# NXPESC-UF1_test003.net
KiCad netlist of a schematic drawn in EAGLE
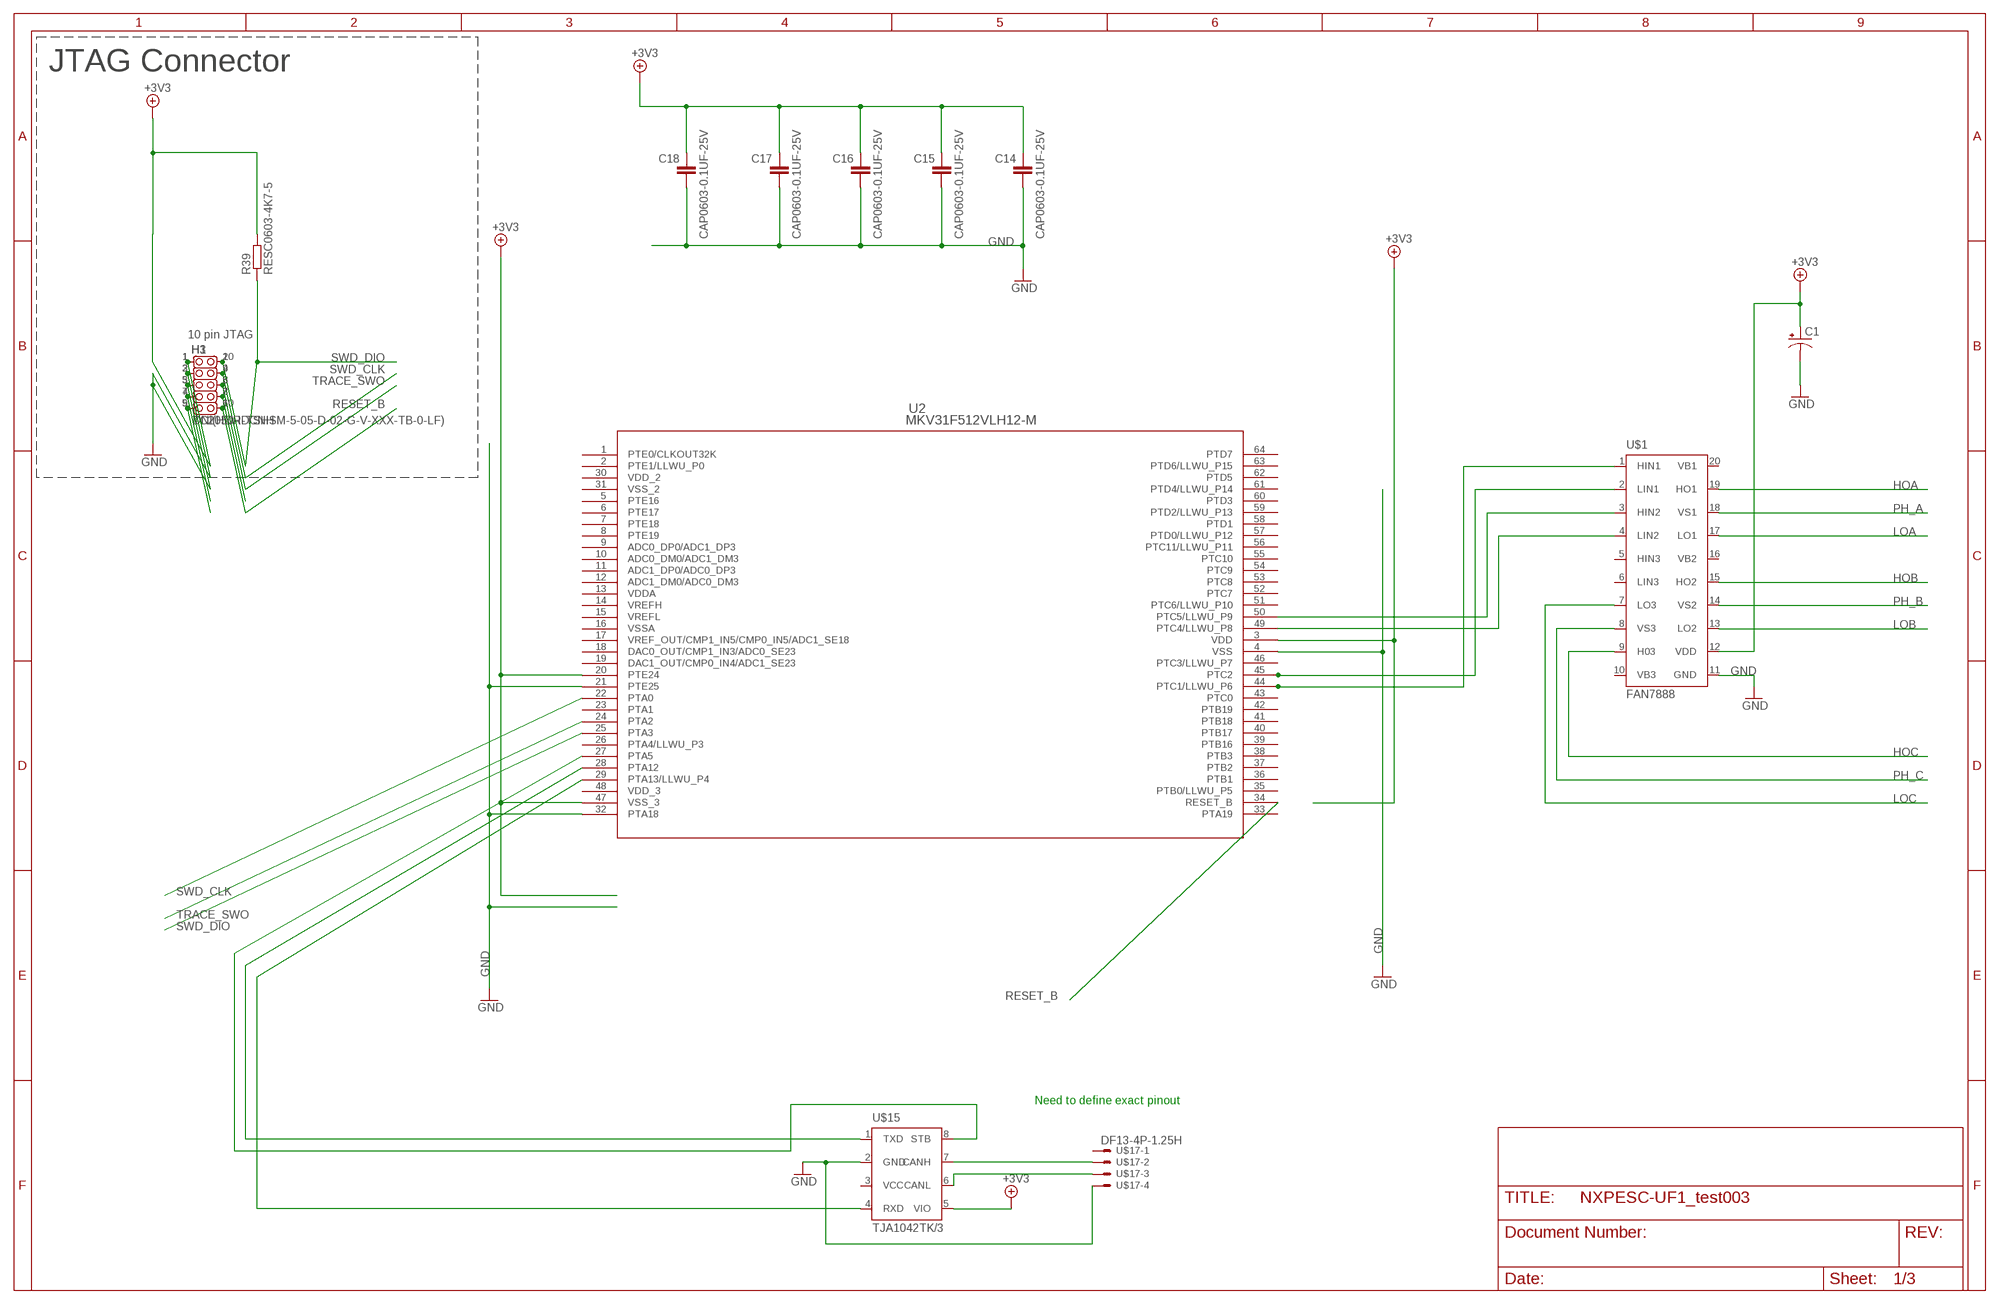
[diagram p0: schematic, sheet 1]
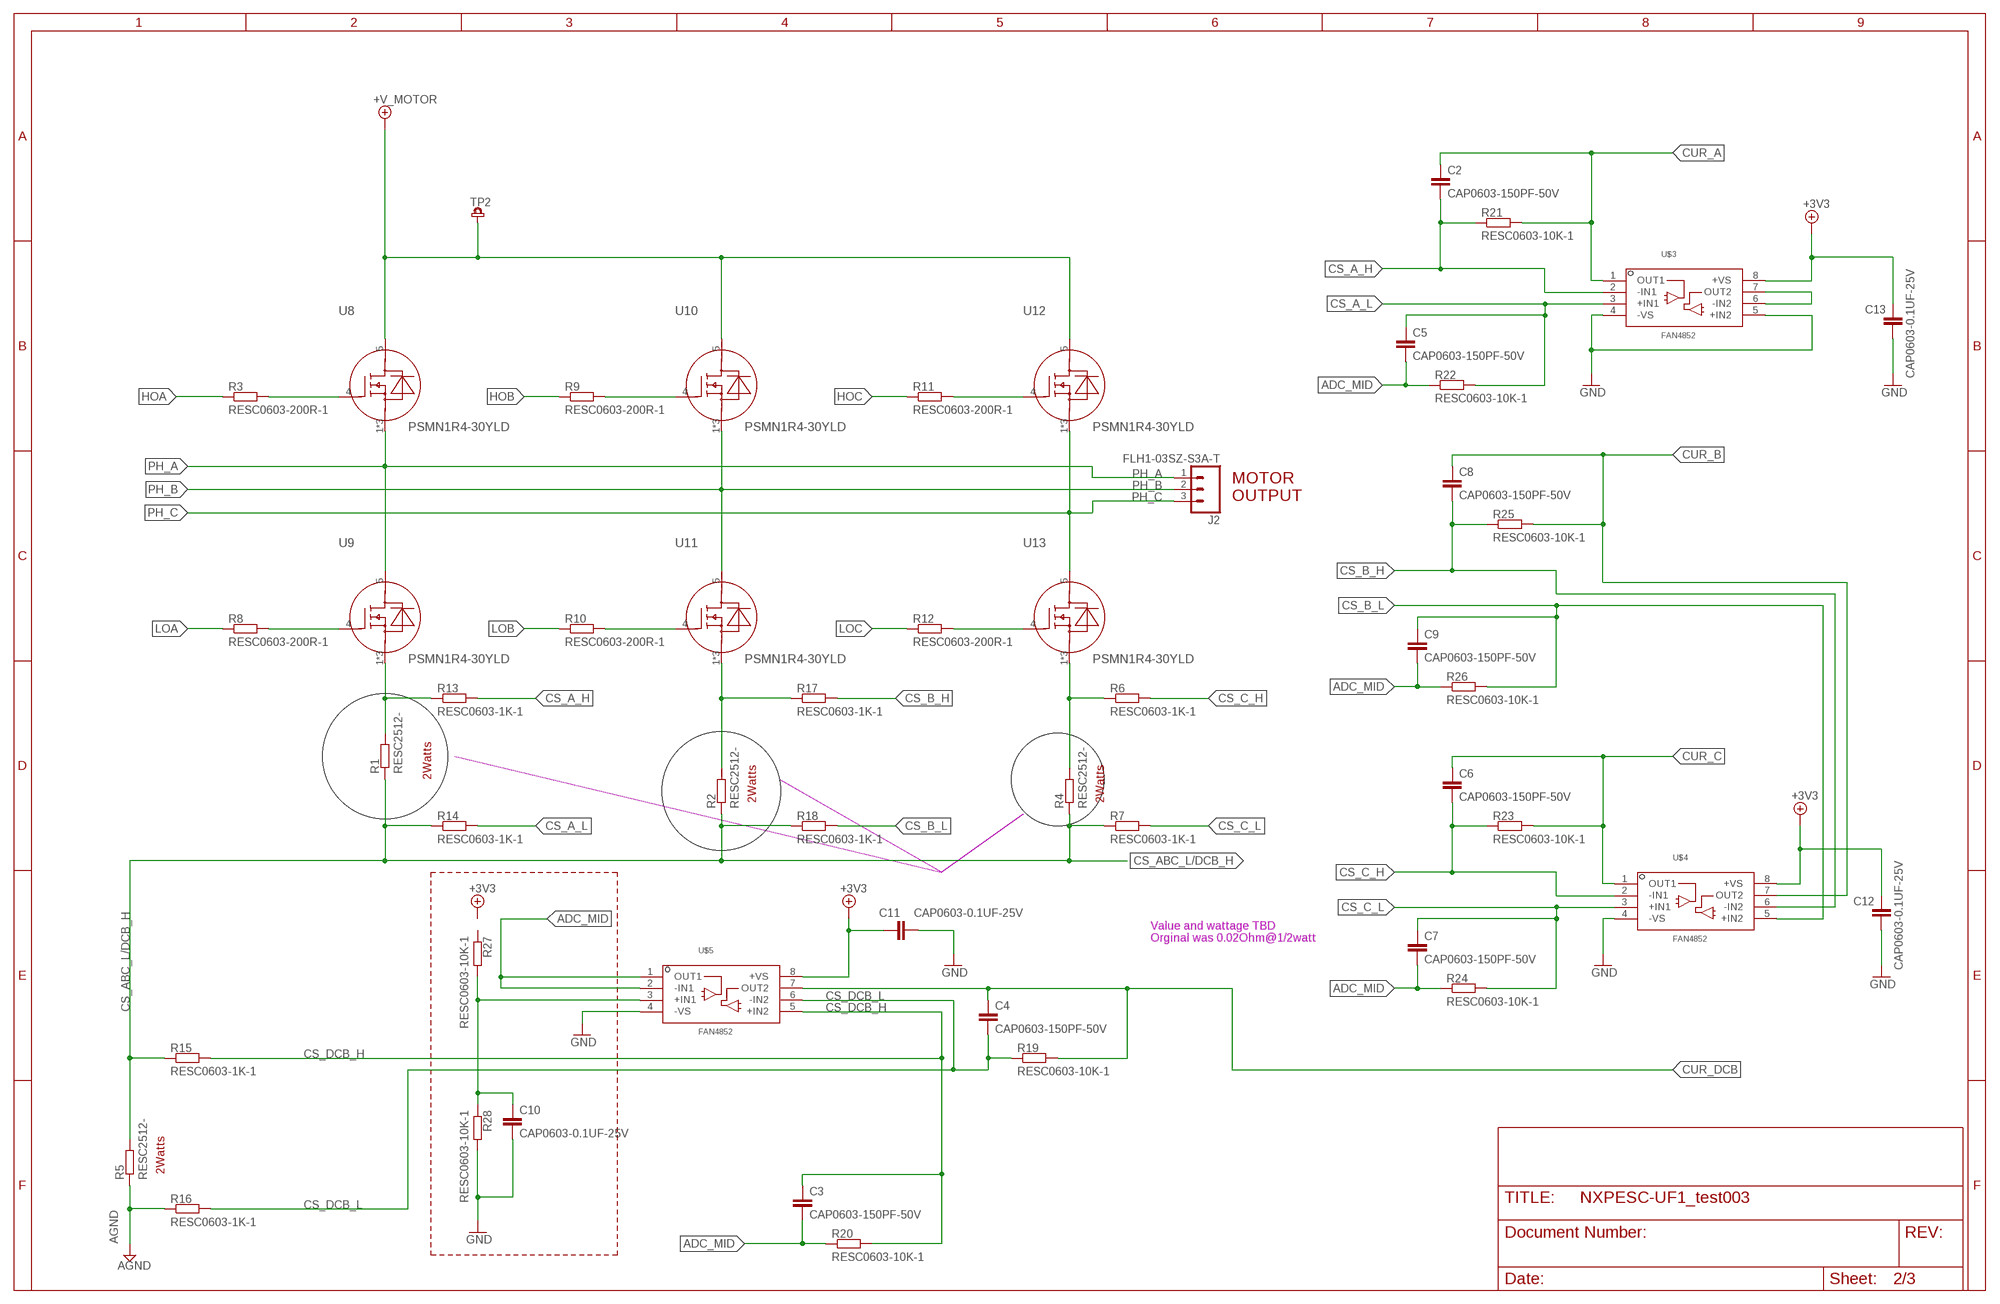
[diagram p1: schematic, sheet 2]
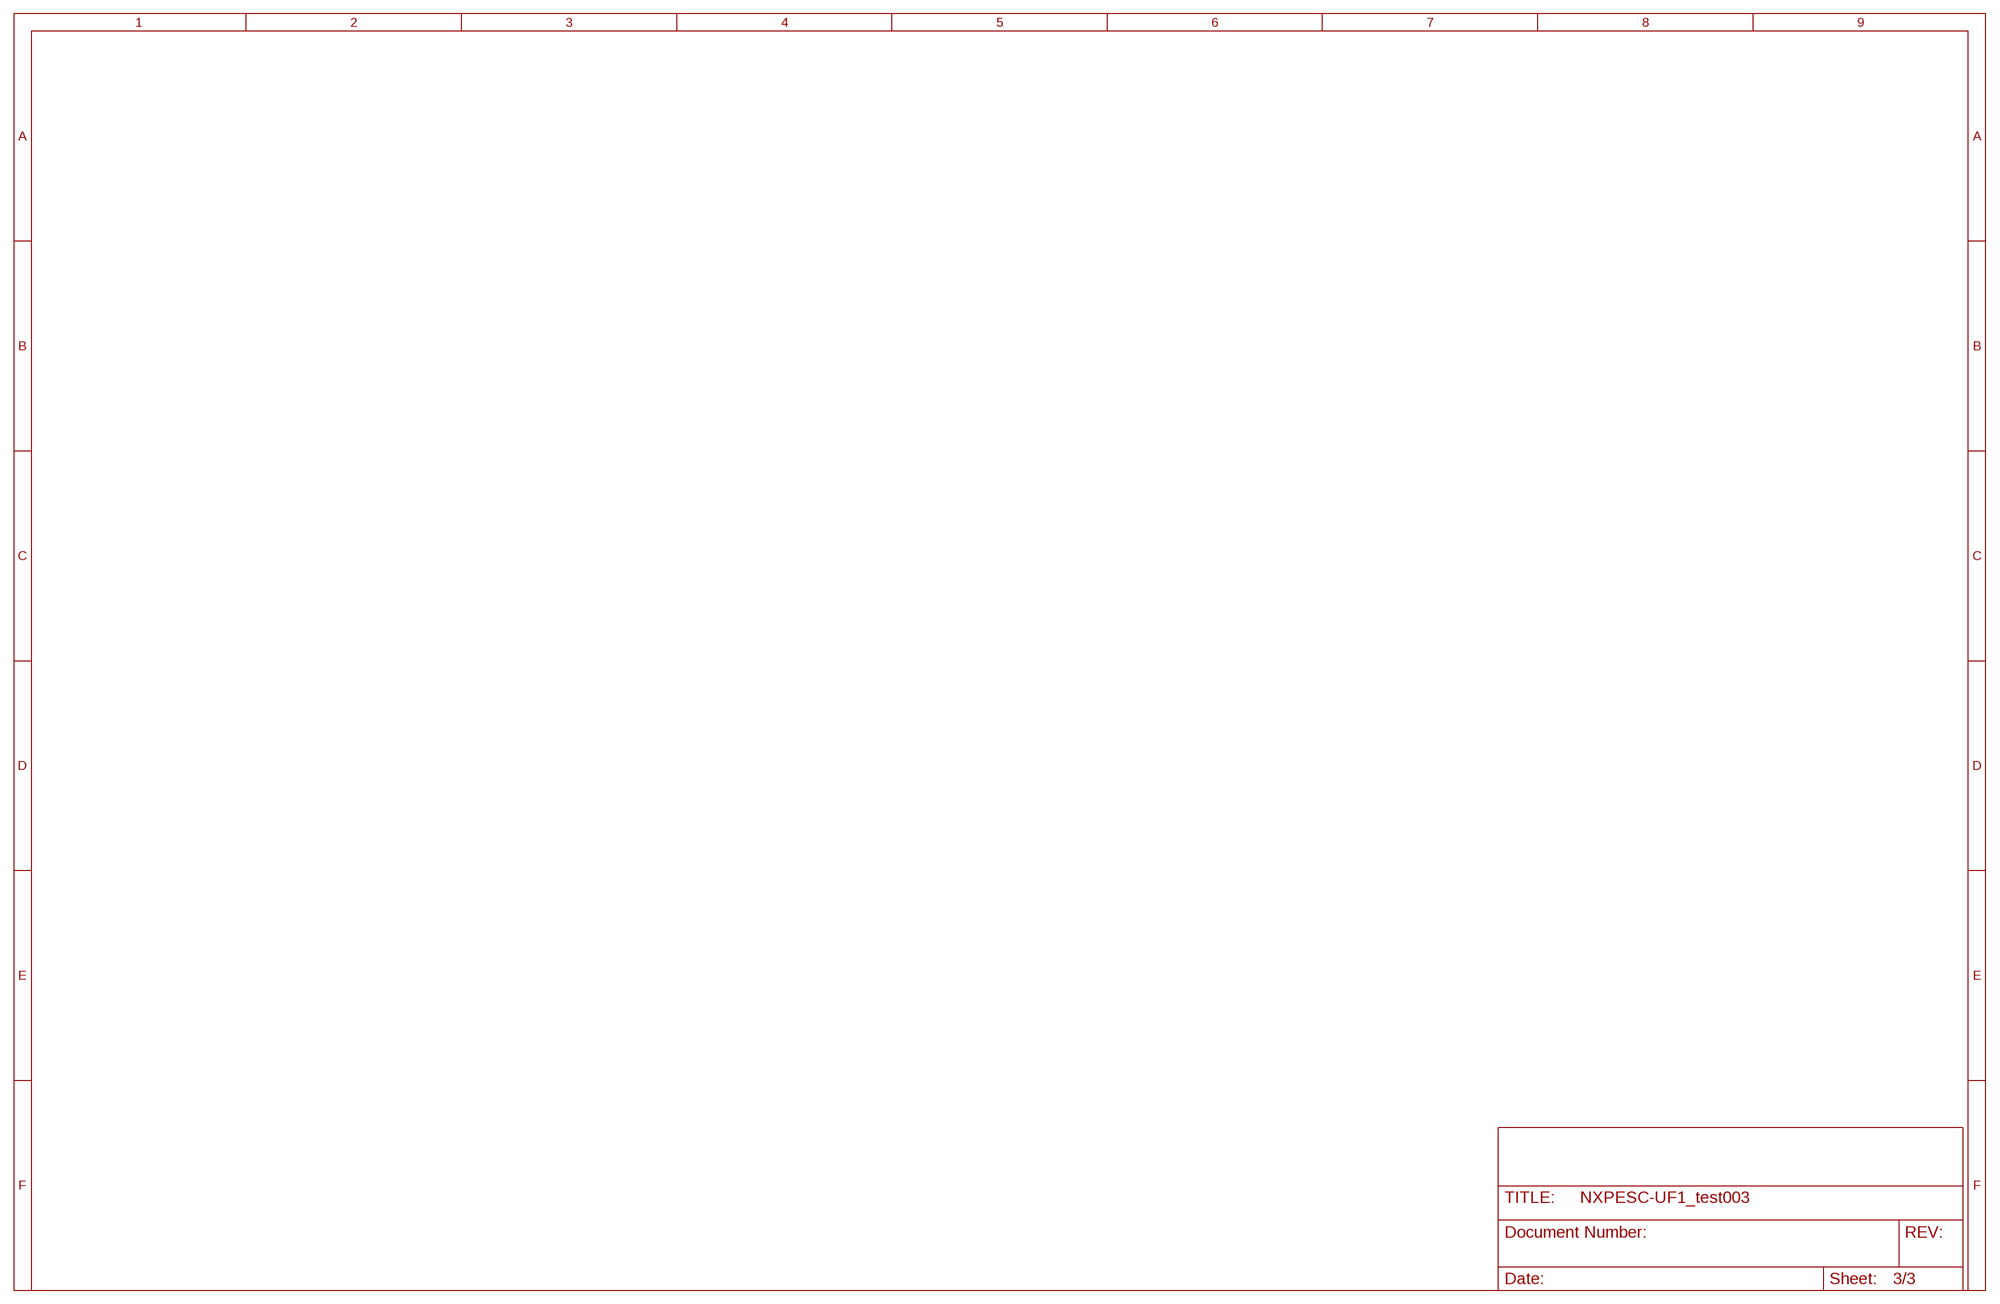
[diagram p2: schematic, sheet 3]

(export (version "E")
  (design (tool "Eeschema 10.0.6"))
  (components
    (comp (ref "C2")
      (value "CAP0603-150PF-50V")
      (footprint "eagle-import:C0603")
      (libsource (lib "eagle-import") (part "CAP?-0603150PF-50V"))
    )
    (comp (ref "C3")
      (value "CAP0603-150PF-50V")
      (footprint "eagle-import:C0603")
      (libsource (lib "eagle-import") (part "CAP?-0603150PF-50V"))
    )
    (comp (ref "C4")
      (value "CAP0603-150PF-50V")
      (footprint "eagle-import:C0603")
      (libsource (lib "eagle-import") (part "CAP?-0603150PF-50V"))
    )
    (comp (ref "C5")
      (value "CAP0603-150PF-50V")
      (footprint "eagle-import:C0603")
      (libsource (lib "eagle-import") (part "CAP?-0603150PF-50V"))
    )
    (comp (ref "C6")
      (value "CAP0603-150PF-50V")
      (footprint "eagle-import:C0603")
      (libsource (lib "eagle-import") (part "CAP?-0603150PF-50V"))
    )
    (comp (ref "C7")
      (value "CAP0603-150PF-50V")
      (footprint "eagle-import:C0603")
      (libsource (lib "eagle-import") (part "CAP?-0603150PF-50V"))
    )
    (comp (ref "C8")
      (value "CAP0603-150PF-50V")
      (footprint "eagle-import:C0603")
      (libsource (lib "eagle-import") (part "CAP?-0603150PF-50V"))
    )
    (comp (ref "C9")
      (value "CAP0603-150PF-50V")
      (footprint "eagle-import:C0603")
      (libsource (lib "eagle-import") (part "CAP?-0603150PF-50V"))
    )
    (comp (ref "C10")
      (value "CAP0603-0.1UF-25V")
      (footprint "eagle-import:C0603")
      (libsource (lib "eagle-import") (part "CAP?-06030.1UF-25V"))
    )
    (comp (ref "C11")
      (value "CAP0603-0.1UF-25V")
      (footprint "eagle-import:C0603")
      (libsource (lib "eagle-import") (part "CAP?-06030.1UF-25V"))
    )
    (comp (ref "C12")
      (value "CAP0603-0.1UF-25V")
      (footprint "eagle-import:C0603")
      (libsource (lib "eagle-import") (part "CAP?-06030.1UF-25V"))
    )
    (comp (ref "C13")
      (value "CAP0603-0.1UF-25V")
      (footprint "eagle-import:C0603")
      (libsource (lib "eagle-import") (part "CAP?-06030.1UF-25V"))
    )
    (comp (ref "J2")
      (value "FLH1-03SZ-S3A-T")
      (footprint "eagle-import:J3")
      (libsource (lib "eagle-import") (part "FLH1-03SZ-S3A-T"))
    )
    (comp (ref "R1")
      (value "RESC2512-")
      (footprint "eagle-import:R2512")
      (libsource (lib "eagle-import") (part "RESC?-2512"))
    )
    (comp (ref "R2")
      (value "RESC2512-")
      (footprint "eagle-import:R2512")
      (libsource (lib "eagle-import") (part "RESC?-2512"))
    )
    (comp (ref "R3")
      (value "RESC0603-200R-1")
      (footprint "eagle-import:C0603")
      (libsource (lib "eagle-import") (part "RESC?-0603200R-1"))
    )
    (comp (ref "R4")
      (value "RESC2512-")
      (footprint "eagle-import:R2512")
      (libsource (lib "eagle-import") (part "RESC?-2512"))
    )
    (comp (ref "R5")
      (value "RESC2512-")
      (footprint "eagle-import:R2512")
      (libsource (lib "eagle-import") (part "RESC?-2512"))
    )
    (comp (ref "R6")
      (value "RESC0603-1K-1")
      (footprint "eagle-import:C0603")
      (libsource (lib "eagle-import") (part "RESC?-06031K-1"))
    )
    (comp (ref "R7")
      (value "RESC0603-1K-1")
      (footprint "eagle-import:C0603")
      (libsource (lib "eagle-import") (part "RESC?-06031K-1"))
    )
    (comp (ref "R8")
      (value "RESC0603-200R-1")
      (footprint "eagle-import:C0603")
      (libsource (lib "eagle-import") (part "RESC?-0603200R-1"))
    )
    (comp (ref "R9")
      (value "RESC0603-200R-1")
      (footprint "eagle-import:C0603")
      (libsource (lib "eagle-import") (part "RESC?-0603200R-1"))
    )
    (comp (ref "R10")
      (value "RESC0603-200R-1")
      (footprint "eagle-import:C0603")
      (libsource (lib "eagle-import") (part "RESC?-0603200R-1"))
    )
    (comp (ref "R11")
      (value "RESC0603-200R-1")
      (footprint "eagle-import:C0603")
      (libsource (lib "eagle-import") (part "RESC?-0603200R-1"))
    )
    (comp (ref "R12")
      (value "RESC0603-200R-1")
      (footprint "eagle-import:C0603")
      (libsource (lib "eagle-import") (part "RESC?-0603200R-1"))
    )
    (comp (ref "R13")
      (value "RESC0603-1K-1")
      (footprint "eagle-import:C0603")
      (libsource (lib "eagle-import") (part "RESC?-06031K-1"))
    )
    (comp (ref "R14")
      (value "RESC0603-1K-1")
      (footprint "eagle-import:C0603")
      (libsource (lib "eagle-import") (part "RESC?-06031K-1"))
    )
    (comp (ref "R15")
      (value "RESC0603-1K-1")
      (footprint "eagle-import:C0603")
      (libsource (lib "eagle-import") (part "RESC?-06031K-1"))
    )
    (comp (ref "R16")
      (value "RESC0603-1K-1")
      (footprint "eagle-import:C0603")
      (libsource (lib "eagle-import") (part "RESC?-06031K-1"))
    )
    (comp (ref "R17")
      (value "RESC0603-1K-1")
      (footprint "eagle-import:C0603")
      (libsource (lib "eagle-import") (part "RESC?-06031K-1"))
    )
    (comp (ref "R18")
      (value "RESC0603-1K-1")
      (footprint "eagle-import:C0603")
      (libsource (lib "eagle-import") (part "RESC?-06031K-1"))
    )
    (comp (ref "R19")
      (value "RESC0603-10K-1")
      (footprint "eagle-import:C0603")
      (libsource (lib "eagle-import") (part "RESC?-060310K-1"))
    )
    (comp (ref "R20")
      (value "RESC0603-10K-1")
      (footprint "eagle-import:C0603")
      (libsource (lib "eagle-import") (part "RESC?-060310K-1"))
    )
    (comp (ref "R21")
      (value "RESC0603-10K-1")
      (footprint "eagle-import:C0603")
      (libsource (lib "eagle-import") (part "RESC?-060310K-1"))
    )
    (comp (ref "R22")
      (value "RESC0603-10K-1")
      (footprint "eagle-import:C0603")
      (libsource (lib "eagle-import") (part "RESC?-060310K-1"))
    )
    (comp (ref "R23")
      (value "RESC0603-10K-1")
      (footprint "eagle-import:C0603")
      (libsource (lib "eagle-import") (part "RESC?-060310K-1"))
    )
    (comp (ref "R24")
      (value "RESC0603-10K-1")
      (footprint "eagle-import:C0603")
      (libsource (lib "eagle-import") (part "RESC?-060310K-1"))
    )
    (comp (ref "R25")
      (value "RESC0603-10K-1")
      (footprint "eagle-import:C0603")
      (libsource (lib "eagle-import") (part "RESC?-060310K-1"))
    )
    (comp (ref "R26")
      (value "RESC0603-10K-1")
      (footprint "eagle-import:C0603")
      (libsource (lib "eagle-import") (part "RESC?-060310K-1"))
    )
    (comp (ref "R27")
      (value "RESC0603-10K-1")
      (footprint "eagle-import:C0603")
      (libsource (lib "eagle-import") (part "RESC?-060310K-1"))
    )
    (comp (ref "R28")
      (value "RESC0603-10K-1")
      (footprint "eagle-import:C0603")
      (libsource (lib "eagle-import") (part "RESC?-060310K-1"))
    )
    (comp (ref "TP2")
      (value "TP-TH-SMLL")
      (footprint "eagle-import:TP-SMLL")
      (libsource (lib "eagle-import") (part "TP-TH-SMLL"))
    )
    (comp (ref "U$3")
      (value "FAN4852")
      (footprint "eagle-import:SOP65P490X110-8N")
      (libsource (lib "eagle-import") (part "FAN4852"))
    )
    (comp (ref "U$4")
      (value "FAN4852")
      (footprint "eagle-import:SOP65P490X110-8N")
      (libsource (lib "eagle-import") (part "FAN4852"))
    )
    (comp (ref "U$5")
      (value "FAN4852")
      (footprint "eagle-import:SOP65P490X110-8N")
      (libsource (lib "eagle-import") (part "FAN4852"))
    )
    (comp (ref "U8")
      (value "PSMN1R4-30YLD")
      (footprint "eagle-import:LFPAK56")
      (libsource (lib "eagle-import") (part "PSMN1R4-30YLD"))
    )
    (comp (ref "U9")
      (value "PSMN1R4-30YLD")
      (footprint "eagle-import:LFPAK56")
      (libsource (lib "eagle-import") (part "PSMN1R4-30YLD"))
    )
    (comp (ref "U10")
      (value "PSMN1R4-30YLD")
      (footprint "eagle-import:LFPAK56")
      (libsource (lib "eagle-import") (part "PSMN1R4-30YLD"))
    )
    (comp (ref "U11")
      (value "PSMN1R4-30YLD")
      (footprint "eagle-import:LFPAK56")
      (libsource (lib "eagle-import") (part "PSMN1R4-30YLD"))
    )
    (comp (ref "U12")
      (value "PSMN1R4-30YLD")
      (footprint "eagle-import:LFPAK56")
      (libsource (lib "eagle-import") (part "PSMN1R4-30YLD"))
    )
    (comp (ref "U13")
      (value "PSMN1R4-30YLD")
      (footprint "eagle-import:LFPAK56")
      (libsource (lib "eagle-import") (part "PSMN1R4-30YLD"))
    )
    (comp (ref "C1")
      (value "CAP_POL1206")
      (footprint "eagle-import:EIA3216")
      (libsource (lib "eagle-import") (part "CAP_POL1206"))
    )
    (comp (ref "C14")
      (value "CAP0603-0.1UF-25V")
      (footprint "eagle-import:C0603")
      (libsource (lib "eagle-import") (part "CAP?-06030.1UF-25V"))
    )
    (comp (ref "C15")
      (value "CAP0603-0.1UF-25V")
      (footprint "eagle-import:C0603")
      (libsource (lib "eagle-import") (part "CAP?-06030.1UF-25V"))
    )
    (comp (ref "C16")
      (value "CAP0603-0.1UF-25V")
      (footprint "eagle-import:C0603")
      (libsource (lib "eagle-import") (part "CAP?-06030.1UF-25V"))
    )
    (comp (ref "C17")
      (value "CAP0603-0.1UF-25V")
      (footprint "eagle-import:C0603")
      (libsource (lib "eagle-import") (part "CAP?-06030.1UF-25V"))
    )
    (comp (ref "C18")
      (value "CAP0603-0.1UF-25V")
      (footprint "eagle-import:C0603")
      (libsource (lib "eagle-import") (part "CAP?-06030.1UF-25V"))
    )
    (comp (ref "H1")
      (value "DNI(HDR-TSHSM-5-05-D-02-G-V-XXX-TB-0-LF)")
      (footprint "eagle-import:HD2X5-SMD-0.05_")
      (libsource (lib "eagle-import") (part "HDR-TSHSM-5--D-02-G-V-XXX-TB-0-LF05"))
    )
    (comp (ref "H3")
      (value "TC2050-IDCNH")
      (footprint "eagle-import:TC2050-IDC-NOHOLES")
      (libsource (lib "eagle-import") (part "TC2050-IDCNH"))
    )
    (comp (ref "R39")
      (value "RESC0603-4K7-5")
      (footprint "eagle-import:C0603")
      (libsource (lib "eagle-import") (part "etc_rcl_RESC?-06034K7-5"))
    )
    (comp (ref "U$1")
      (value "FAN7888")
      (footprint "eagle-import:SOIC-20")
      (libsource (lib "eagle-import") (part "FAN7888"))
    )
    (comp (ref "U$15")
      (value "TJA1042TK/3")
      (footprint "eagle-import:HVSON8")
      (libsource (lib "eagle-import") (part "TJA1042TK/3"))
    )
    (comp (ref "U$17")
      (value "DF13-4P-1.25H")
      (footprint "eagle-import:DF13A-4P-1.25H")
      (libsource (lib "eagle-import") (part "DF13-4P-1.25?H"))
    )
    (comp (ref "U2")
      (value "MKV31F512VLH12-M")
      (footprint "eagle-import:LQFP-64_10X10X1_6-M")
      (libsource (lib "eagle-import") (part "MKV31F512VLH12-M"))
    )
  )
  (nets
    (net (code "1") (name "+3V3") (class "Default")
      (node (ref "C1") (pin "A") (pinfunction "+_A") (pintype "passive"))
      (node (ref "C11") (pin "1") (pinfunction "1_1") (pintype "passive"))
      (node (ref "C12") (pin "1") (pinfunction "1_1") (pintype "passive"))
      (node (ref "C13") (pin "1") (pinfunction "1_1") (pintype "passive"))
      (node (ref "C14") (pin "1") (pinfunction "1_1") (pintype "passive"))
      (node (ref "C15") (pin "1") (pinfunction "1_1") (pintype "passive"))
      (node (ref "C16") (pin "1") (pinfunction "1_1") (pintype "passive"))
      (node (ref "C17") (pin "1") (pinfunction "1_1") (pintype "passive"))
      (node (ref "C18") (pin "1") (pinfunction "1_1") (pintype "passive"))
      (node (ref "H1") (pin "1") (pinfunction "1_1") (pintype "passive"))
      (node (ref "H3") (pin "1") (pinfunction "VCC_1") (pintype "passive"))
      (node (ref "R39") (pin "2") (pinfunction "2_2") (pintype "passive"))
      (node (ref "U$1") (pin "12") (pinfunction "VDD_12") (pintype "power_in"))
      (node (ref "U$15") (pin "5") (pinfunction "VIO_5") (pintype "power_in"))
      (node (ref "U$3") (pin "8") (pinfunction "+VS_8") (pintype "passive"))
      (node (ref "U$4") (pin "8") (pinfunction "+VS_8") (pintype "passive"))
      (node (ref "U$5") (pin "8") (pinfunction "+VS_8") (pintype "passive"))
      (node (ref "U2") (pin "20") (pinfunction "PTE24_20") (pintype "bidirectional"))
      (node (ref "U2") (pin "3") (pinfunction "VDD_3") (pintype "power_in"))
      (node (ref "U2") (pin "47") (pinfunction "VSS_3_47") (pintype "power_in"))
    )
    (net (code "2") (name "+V_MOTOR") (class "Default")
      (node (ref "TP2") (pin "1") (pinfunction "1_1") (pintype "passive"))
      (node (ref "U10") (pin "5") (pinfunction "D_5") (pintype "open_collector"))
      (node (ref "U12") (pin "5") (pinfunction "D_5") (pintype "open_collector"))
      (node (ref "U8") (pin "5") (pinfunction "D_5") (pintype "open_collector"))
    )
    (net (code "3") (name "ADC_MID") (class "Default")
      (node (ref "C3") (pin "2") (pinfunction "2_2") (pintype "passive"))
      (node (ref "C5") (pin "2") (pinfunction "2_2") (pintype "passive"))
      (node (ref "C7") (pin "2") (pinfunction "2_2") (pintype "passive"))
      (node (ref "C9") (pin "2") (pinfunction "2_2") (pintype "passive"))
      (node (ref "R20") (pin "1") (pinfunction "1_1") (pintype "passive"))
      (node (ref "R22") (pin "1") (pinfunction "1_1") (pintype "passive"))
      (node (ref "R24") (pin "1") (pinfunction "1_1") (pintype "passive"))
      (node (ref "R26") (pin "1") (pinfunction "1_1") (pintype "passive"))
      (node (ref "U$5") (pin "1") (pinfunction "OUT1_1") (pintype "output"))
      (node (ref "U$5") (pin "2") (pinfunction "-IN1_2") (pintype "input"))
    )
    (net (code "4") (name "AGND") (class "Default")
      (node (ref "R16") (pin "1") (pinfunction "1_1") (pintype "passive"))
      (node (ref "R5") (pin "1") (pinfunction "1_1") (pintype "passive"))
    )
    (net (code "5") (name "CS_ABC_L{slash}DCB_H") (class "Default")
      (node (ref "R1") (pin "1") (pinfunction "1_1") (pintype "passive"))
      (node (ref "R14") (pin "1") (pinfunction "1_1") (pintype "passive"))
      (node (ref "R15") (pin "1") (pinfunction "1_1") (pintype "passive"))
      (node (ref "R18") (pin "1") (pinfunction "1_1") (pintype "passive"))
      (node (ref "R2") (pin "1") (pinfunction "1_1") (pintype "passive"))
      (node (ref "R4") (pin "1") (pinfunction "1_1") (pintype "passive"))
      (node (ref "R5") (pin "2") (pinfunction "2_2") (pintype "passive"))
      (node (ref "R7") (pin "1") (pinfunction "1_1") (pintype "passive"))
    )
    (net (code "6") (name "CS_A_H") (class "Default")
      (node (ref "C2") (pin "2") (pinfunction "2_2") (pintype "passive"))
      (node (ref "R13") (pin "2") (pinfunction "2_2") (pintype "passive"))
      (node (ref "R21") (pin "1") (pinfunction "1_1") (pintype "passive"))
      (node (ref "U$3") (pin "2") (pinfunction "-IN1_2") (pintype "input"))
    )
    (net (code "7") (name "CS_A_L") (class "Default")
      (node (ref "C5") (pin "1") (pinfunction "1_1") (pintype "passive"))
      (node (ref "R14") (pin "2") (pinfunction "2_2") (pintype "passive"))
      (node (ref "R22") (pin "2") (pinfunction "2_2") (pintype "passive"))
      (node (ref "U$3") (pin "3") (pinfunction "+IN1_3") (pintype "input"))
    )
    (net (code "8") (name "CS_B_H") (class "Default")
      (node (ref "C8") (pin "2") (pinfunction "2_2") (pintype "passive"))
      (node (ref "R17") (pin "2") (pinfunction "2_2") (pintype "passive"))
      (node (ref "R25") (pin "1") (pinfunction "1_1") (pintype "passive"))
      (node (ref "U$4") (pin "6") (pinfunction "-IN2_6") (pintype "input"))
    )
    (net (code "9") (name "CS_B_L") (class "Default")
      (node (ref "C9") (pin "1") (pinfunction "1_1") (pintype "passive"))
      (node (ref "R18") (pin "2") (pinfunction "2_2") (pintype "passive"))
      (node (ref "R26") (pin "2") (pinfunction "2_2") (pintype "passive"))
      (node (ref "U$4") (pin "5") (pinfunction "+IN2_5") (pintype "input"))
    )
    (net (code "10") (name "CS_C_H") (class "Default")
      (node (ref "C6") (pin "2") (pinfunction "2_2") (pintype "passive"))
      (node (ref "R23") (pin "1") (pinfunction "1_1") (pintype "passive"))
      (node (ref "R6") (pin "2") (pinfunction "2_2") (pintype "passive"))
      (node (ref "U$4") (pin "2") (pinfunction "-IN1_2") (pintype "input"))
    )
    (net (code "11") (name "CS_C_L") (class "Default")
      (node (ref "C7") (pin "1") (pinfunction "1_1") (pintype "passive"))
      (node (ref "R24") (pin "2") (pinfunction "2_2") (pintype "passive"))
      (node (ref "R7") (pin "2") (pinfunction "2_2") (pintype "passive"))
      (node (ref "U$4") (pin "3") (pinfunction "+IN1_3") (pintype "input"))
    )
    (net (code "12") (name "CS_DCB_H") (class "Default")
      (node (ref "C3") (pin "1") (pinfunction "1_1") (pintype "passive"))
      (node (ref "R15") (pin "2") (pinfunction "2_2") (pintype "passive"))
      (node (ref "R20") (pin "2") (pinfunction "2_2") (pintype "passive"))
      (node (ref "U$5") (pin "5") (pinfunction "+IN2_5") (pintype "input"))
    )
    (net (code "13") (name "CS_DCB_L") (class "Default")
      (node (ref "C4") (pin "2") (pinfunction "2_2") (pintype "passive"))
      (node (ref "R16") (pin "2") (pinfunction "2_2") (pintype "passive"))
      (node (ref "R19") (pin "1") (pinfunction "1_1") (pintype "passive"))
      (node (ref "U$5") (pin "6") (pinfunction "-IN2_6") (pintype "input"))
    )
    (net (code "14") (name "CUR_A") (class "Default")
      (node (ref "C2") (pin "1") (pinfunction "1_1") (pintype "passive"))
      (node (ref "R21") (pin "2") (pinfunction "2_2") (pintype "passive"))
      (node (ref "U$3") (pin "1") (pinfunction "OUT1_1") (pintype "output"))
    )
    (net (code "15") (name "CUR_B") (class "Default")
      (node (ref "C8") (pin "1") (pinfunction "1_1") (pintype "passive"))
      (node (ref "R25") (pin "2") (pinfunction "2_2") (pintype "passive"))
      (node (ref "U$4") (pin "7") (pinfunction "OUT2_7") (pintype "output"))
    )
    (net (code "16") (name "CUR_C") (class "Default")
      (node (ref "C6") (pin "1") (pinfunction "1_1") (pintype "passive"))
      (node (ref "R23") (pin "2") (pinfunction "2_2") (pintype "passive"))
      (node (ref "U$4") (pin "1") (pinfunction "OUT1_1") (pintype "output"))
    )
    (net (code "17") (name "CUR_DCB") (class "Default")
      (node (ref "C4") (pin "1") (pinfunction "1_1") (pintype "passive"))
      (node (ref "R19") (pin "2") (pinfunction "2_2") (pintype "passive"))
      (node (ref "U$5") (pin "7") (pinfunction "OUT2_7") (pintype "output"))
    )
    (net (code "18") (name "GND") (class "Default")
      (node (ref "C1") (pin "C") (pinfunction "-_C") (pintype "passive"))
      (node (ref "C10") (pin "2") (pinfunction "2_2") (pintype "passive"))
      (node (ref "C11") (pin "2") (pinfunction "2_2") (pintype "passive"))
      (node (ref "C12") (pin "2") (pinfunction "2_2") (pintype "passive"))
      (node (ref "C13") (pin "2") (pinfunction "2_2") (pintype "passive"))
      (node (ref "C14") (pin "2") (pinfunction "2_2") (pintype "passive"))
      (node (ref "C15") (pin "2") (pinfunction "2_2") (pintype "passive"))
      (node (ref "C16") (pin "2") (pinfunction "2_2") (pintype "passive"))
      (node (ref "C17") (pin "2") (pinfunction "2_2") (pintype "passive"))
      (node (ref "C18") (pin "2") (pinfunction "2_2") (pintype "passive"))
      (node (ref "H1") (pin "3") (pinfunction "3_3") (pintype "passive"))
      (node (ref "H1") (pin "5") (pinfunction "5_5") (pintype "passive"))
      (node (ref "H3") (pin "2") (pinfunction "TMS_2") (pintype "passive"))
      (node (ref "H3") (pin "3") (pinfunction "GND_3") (pintype "passive"))
      (node (ref "R28") (pin "2") (pinfunction "2_2") (pintype "passive"))
      (node (ref "U$1") (pin "11") (pinfunction "GND_11") (pintype "passive"))
      (node (ref "U$15") (pin "2") (pinfunction "GND_2") (pintype "passive"))
      (node (ref "U$17") (pin "4") (pinfunction "S_4") (pintype "passive"))
      (node (ref "U$3") (pin "4") (pinfunction "-VS_4") (pintype "passive"))
      (node (ref "U$3") (pin "5") (pinfunction "+IN2_5") (pintype "input"))
      (node (ref "U$4") (pin "4") (pinfunction "-VS_4") (pintype "passive"))
      (node (ref "U$5") (pin "4") (pinfunction "-VS_4") (pintype "passive"))
      (node (ref "U2") (pin "21") (pinfunction "PTE25_21") (pintype "bidirectional"))
      (node (ref "U2") (pin "32") (pinfunction "PTA18_32") (pintype "bidirectional"))
      (node (ref "U2") (pin "4") (pinfunction "VSS_4") (pintype "power_in"))
    )
    (net (code "19") (name "HOA") (class "Default")
      (node (ref "R3") (pin "1") (pinfunction "1_1") (pintype "passive"))
      (node (ref "U$1") (pin "19") (pinfunction "HO1_19") (pintype "output"))
    )
    (net (code "20") (name "HOB") (class "Default")
      (node (ref "R9") (pin "1") (pinfunction "1_1") (pintype "passive"))
      (node (ref "U$1") (pin "15") (pinfunction "HO2_15") (pintype "output"))
    )
    (net (code "21") (name "HOC") (class "Default")
      (node (ref "R11") (pin "1") (pinfunction "1_1") (pintype "passive"))
      (node (ref "U$1") (pin "9") (pinfunction "H03_9") (pintype "output"))
    )
    (net (code "22") (name "LOA") (class "Default")
      (node (ref "R8") (pin "1") (pinfunction "1_1") (pintype "passive"))
      (node (ref "U$1") (pin "17") (pinfunction "LO1_17") (pintype "output"))
    )
    (net (code "23") (name "LOB") (class "Default")
      (node (ref "R10") (pin "1") (pinfunction "1_1") (pintype "passive"))
      (node (ref "U$1") (pin "13") (pinfunction "LO2_13") (pintype "output"))
    )
    (net (code "24") (name "LOC") (class "Default")
      (node (ref "R12") (pin "1") (pinfunction "1_1") (pintype "passive"))
      (node (ref "U$1") (pin "7") (pinfunction "LO3_7") (pintype "output"))
    )
    (net (code "25") (name "Net-(H1-Pad8)") (class "Default")
      (node (ref "H1") (pin "8") (pinfunction "8_8") (pintype "passive"))
      (node (ref "H3") (pin "7") (pinfunction "NOTUSED_7") (pintype "passive"))
    )
    (net (code "26") (name "Net-(H3-GND{slash}+5V)") (class "Default")
      (node (ref "H1") (pin "9") (pinfunction "9_9") (pintype "passive"))
      (node (ref "H3") (pin "5") (pinfunction "GND/+5V_5") (pintype "passive"))
    )
    (net (code "27") (name "Net-(H3-TCK)") (class "Default")
      (node (ref "H1") (pin "7") (pinfunction "7_7") (pintype "passive"))
      (node (ref "H3") (pin "4") (pinfunction "TCK_4") (pintype "passive"))
    )
    (net (code "28") (name "Net-(R1-Pad2)") (class "Default")
      (node (ref "R1") (pin "2") (pinfunction "2_2") (pintype "passive"))
      (node (ref "R13") (pin "1") (pinfunction "1_1") (pintype "passive"))
      (node (ref "U9") (pin "1") (pinfunction "S_1") (pintype "passive"))
      (node (ref "U9") (pin "2") (pinfunction "S_2") (pintype "passive"))
      (node (ref "U9") (pin "3") (pinfunction "S_3") (pintype "passive"))
    )
    (net (code "29") (name "Net-(R4-Pad2)") (class "Default")
      (node (ref "R4") (pin "2") (pinfunction "2_2") (pintype "passive"))
      (node (ref "R6") (pin "1") (pinfunction "1_1") (pintype "passive"))
      (node (ref "U13") (pin "1") (pinfunction "S_1") (pintype "passive"))
      (node (ref "U13") (pin "2") (pinfunction "S_2") (pintype "passive"))
      (node (ref "U13") (pin "3") (pinfunction "S_3") (pintype "passive"))
    )
    (net (code "30") (name "Net-(R17-Pad1)") (class "Default")
      (node (ref "R17") (pin "1") (pinfunction "1_1") (pintype "passive"))
      (node (ref "R2") (pin "2") (pinfunction "2_2") (pintype "passive"))
      (node (ref "U11") (pin "1") (pinfunction "S_1") (pintype "passive"))
      (node (ref "U11") (pin "2") (pinfunction "S_2") (pintype "passive"))
      (node (ref "U11") (pin "3") (pinfunction "S_3") (pintype "passive"))
    )
    (net (code "31") (name "Net-(U$1-HIN1)") (class "Default")
      (node (ref "U$1") (pin "1") (pinfunction "HIN1_1") (pintype "input"))
      (node (ref "U2") (pin "44") (pinfunction "PTC1/LLWU_P6_44") (pintype "bidirectional"))
    )
    (net (code "32") (name "Net-(U$1-HIN2)") (class "Default")
      (node (ref "U$1") (pin "3") (pinfunction "HIN2_3") (pintype "input"))
      (node (ref "U2") (pin "50") (pinfunction "PTC5/LLWU_P9_50") (pintype "bidirectional"))
    )
    (net (code "33") (name "Net-(U$1-LIN1)") (class "Default")
      (node (ref "U$1") (pin "2") (pinfunction "LIN1_2") (pintype "input"))
      (node (ref "U2") (pin "45") (pinfunction "PTC2_45") (pintype "bidirectional"))
    )
    (net (code "34") (name "Net-(U$1-LIN2)") (class "Default")
      (node (ref "U$1") (pin "4") (pinfunction "LIN2_4") (pintype "input"))
      (node (ref "U2") (pin "49") (pinfunction "PTC4/LLWU_P8_49") (pintype "bidirectional"))
    )
    (net (code "35") (name "Net-(U$3--IN2)") (class "Default")
      (node (ref "U$3") (pin "6") (pinfunction "-IN2_6") (pintype "input"))
      (node (ref "U$3") (pin "7") (pinfunction "OUT2_7") (pintype "output"))
    )
    (net (code "36") (name "Net-(U$5-+IN1)") (class "Default")
      (node (ref "C10") (pin "1") (pinfunction "1_1") (pintype "passive"))
      (node (ref "R27") (pin "2") (pinfunction "2_2") (pintype "passive"))
      (node (ref "R28") (pin "1") (pinfunction "1_1") (pintype "passive"))
      (node (ref "U$5") (pin "3") (pinfunction "+IN1_3") (pintype "input"))
    )
    (net (code "37") (name "Net-(U$15-CANH)") (class "Default")
      (node (ref "U$15") (pin "7") (pinfunction "CANH_7") (pintype "output"))
      (node (ref "U$17") (pin "2") (pinfunction "S_2") (pintype "passive"))
    )
    (net (code "38") (name "Net-(U$15-CANL)") (class "Default")
      (node (ref "U$15") (pin "6") (pinfunction "CANL_6") (pintype "output"))
      (node (ref "U$17") (pin "3") (pinfunction "S_3") (pintype "passive"))
    )
    (net (code "39") (name "Net-(U$15-RXD)") (class "Default")
      (node (ref "U$15") (pin "4") (pinfunction "RXD_4") (pintype "output"))
      (node (ref "U2") (pin "29") (pinfunction "PTA13/LLWU_P4_29") (pintype "bidirectional"))
    )
    (net (code "40") (name "Net-(U$15-STB)") (class "Default")
      (node (ref "U$15") (pin "8") (pinfunction "STB_8") (pintype "input"))
      (node (ref "U2") (pin "27") (pinfunction "PTA5_27") (pintype "bidirectional"))
    )
    (net (code "41") (name "Net-(U$15-TXD)") (class "Default")
      (node (ref "U$15") (pin "1") (pinfunction "TXD_1") (pintype "input"))
      (node (ref "U2") (pin "28") (pinfunction "PTA12_28") (pintype "bidirectional"))
    )
    (net (code "42") (name "Net-(U8-G)") (class "Default")
      (node (ref "R3") (pin "2") (pinfunction "2_2") (pintype "passive"))
      (node (ref "U8") (pin "4") (pinfunction "G_4") (pintype "input"))
    )
    (net (code "43") (name "Net-(U9-G)") (class "Default")
      (node (ref "R8") (pin "2") (pinfunction "2_2") (pintype "passive"))
      (node (ref "U9") (pin "4") (pinfunction "G_4") (pintype "input"))
    )
    (net (code "44") (name "Net-(U10-G)") (class "Default")
      (node (ref "R9") (pin "2") (pinfunction "2_2") (pintype "passive"))
      (node (ref "U10") (pin "4") (pinfunction "G_4") (pintype "input"))
    )
    (net (code "45") (name "Net-(U11-G)") (class "Default")
      (node (ref "R10") (pin "2") (pinfunction "2_2") (pintype "passive"))
      (node (ref "U11") (pin "4") (pinfunction "G_4") (pintype "input"))
    )
    (net (code "46") (name "Net-(U12-G)") (class "Default")
      (node (ref "R11") (pin "2") (pinfunction "2_2") (pintype "passive"))
      (node (ref "U12") (pin "4") (pinfunction "G_4") (pintype "input"))
    )
    (net (code "47") (name "Net-(U13-G)") (class "Default")
      (node (ref "R12") (pin "2") (pinfunction "2_2") (pintype "passive"))
      (node (ref "U13") (pin "4") (pinfunction "G_4") (pintype "input"))
    )
    (net (code "48") (name "PH_A") (class "Default")
      (node (ref "J2") (pin "1") (pinfunction "1_1") (pintype "passive"))
      (node (ref "U$1") (pin "18") (pinfunction "VS1_18") (pintype "power_in"))
      (node (ref "U8") (pin "1") (pinfunction "S_1") (pintype "passive"))
      (node (ref "U8") (pin "2") (pinfunction "S_2") (pintype "passive"))
      (node (ref "U8") (pin "3") (pinfunction "S_3") (pintype "passive"))
      (node (ref "U9") (pin "5") (pinfunction "D_5") (pintype "open_collector"))
    )
    (net (code "49") (name "PH_B") (class "Default")
      (node (ref "J2") (pin "2") (pinfunction "2_2") (pintype "passive"))
      (node (ref "U$1") (pin "14") (pinfunction "VS2_14") (pintype "power_in"))
      (node (ref "U10") (pin "1") (pinfunction "S_1") (pintype "passive"))
      (node (ref "U10") (pin "2") (pinfunction "S_2") (pintype "passive"))
      (node (ref "U10") (pin "3") (pinfunction "S_3") (pintype "passive"))
      (node (ref "U11") (pin "5") (pinfunction "D_5") (pintype "open_collector"))
    )
    (net (code "50") (name "PH_C") (class "Default")
      (node (ref "J2") (pin "3") (pinfunction "3_3") (pintype "passive"))
      (node (ref "U$1") (pin "8") (pinfunction "VS3_8") (pintype "power_in"))
      (node (ref "U12") (pin "1") (pinfunction "S_1") (pintype "passive"))
      (node (ref "U12") (pin "2") (pinfunction "S_2") (pintype "passive"))
      (node (ref "U12") (pin "3") (pinfunction "S_3") (pintype "passive"))
      (node (ref "U13") (pin "5") (pinfunction "D_5") (pintype "open_collector"))
    )
    (net (code "51") (name "RESET_B") (class "Default")
      (node (ref "H1") (pin "10") (pinfunction "10_10") (pintype "passive"))
      (node (ref "H3") (pin "6") (pinfunction "TDO_6") (pintype "passive"))
      (node (ref "U2") (pin "34") (pinfunction "RESET_B_34") (pintype "passive"))
    )
    (net (code "52") (name "SWD_CLK") (class "Default")
      (node (ref "H1") (pin "4") (pinfunction "4_4") (pintype "passive"))
      (node (ref "H3") (pin "9") (pinfunction "NOTUSED_9") (pintype "passive"))
      (node (ref "U2") (pin "22") (pinfunction "PTA0_22") (pintype "bidirectional"))
    )
    (net (code "53") (name "SWD_DIO") (class "Default")
      (node (ref "H1") (pin "2") (pinfunction "2_2") (pintype "passive"))
      (node (ref "H3") (pin "10") (pinfunction "RESET_10") (pintype "passive"))
      (node (ref "R39") (pin "1") (pinfunction "1_1") (pintype "passive"))
      (node (ref "U2") (pin "25") (pinfunction "PTA3_25") (pintype "bidirectional"))
    )
    (net (code "54") (name "TRACE_SWO") (class "Default")
      (node (ref "H1") (pin "6") (pinfunction "6_6") (pintype "passive"))
      (node (ref "H3") (pin "8") (pinfunction "TDI_8") (pintype "passive"))
      (node (ref "U2") (pin "24") (pinfunction "PTA2_24") (pintype "bidirectional"))
    )
    (net (code "55") (name "VB1") (class "Default")
      (node (ref "U$1") (pin "20") (pinfunction "VB1_20") (pintype "power_in"))
    )
    (net (code "56") (name "VB2") (class "Default")
      (node (ref "U$1") (pin "16") (pinfunction "VB2_16") (pintype "power_in"))
    )
    (net (code "57") (name "VB3") (class "Default")
      (node (ref "U$1") (pin "10") (pinfunction "VB3_10") (pintype "power_in"))
    )
    (net (code "58") (name "VCC") (class "Default")
      (node (ref "U$15") (pin "3") (pinfunction "VCC_3") (pintype "power_in"))
    )
    (net (code "59") (name "VDDA") (class "Default")
      (node (ref "U2") (pin "13") (pinfunction "VDDA_13") (pintype "power_in"))
    )
    (net (code "60") (name "VDD_2") (class "Default")
      (node (ref "U2") (pin "30") (pinfunction "VDD_2_30") (pintype "power_in"))
    )
    (net (code "61") (name "VDD_3") (class "Default")
      (node (ref "U2") (pin "48") (pinfunction "VDD_3_48") (pintype "power_in"))
    )
    (net (code "62") (name "VREFH") (class "Default")
      (node (ref "U2") (pin "14") (pinfunction "VREFH_14") (pintype "power_in"))
    )
    (net (code "63") (name "VREFL") (class "Default")
      (node (ref "U2") (pin "15") (pinfunction "VREFL_15") (pintype "power_in"))
    )
    (net (code "64") (name "VSSA") (class "Default")
      (node (ref "U2") (pin "16") (pinfunction "VSSA_16") (pintype "power_in"))
    )
    (net (code "65") (name "VSS_2") (class "Default")
      (node (ref "U2") (pin "31") (pinfunction "VSS_2_31") (pintype "power_in"))
    )
    (net (code "66") (name "unconnected-(R27-Pad1)") (class "Default")
      (node (ref "R27") (pin "1") (pinfunction "1_1") (pintype "passive"))
    )
    (net (code "67") (name "unconnected-(U$1-HIN3-Pad5)") (class "Default")
      (node (ref "U$1") (pin "5") (pinfunction "HIN3_5") (pintype "input"))
    )
    (net (code "68") (name "unconnected-(U$1-LIN3-Pad6)") (class "Default")
      (node (ref "U$1") (pin "6") (pinfunction "LIN3_6") (pintype "input"))
    )
    (net (code "69") (name "unconnected-(U$17A-S-Pad1)") (class "Default")
      (node (ref "U$17") (pin "1") (pinfunction "S_1") (pintype "passive"))
    )
    (net (code "70") (name "unconnected-(U2-ADC0_DM0{slash}ADC1_DM3-Pad10)") (class "Default")
      (node (ref "U2") (pin "10") (pinfunction "ADC0_DM0/ADC1_DM3_10") (pintype "bidirectional"))
    )
    (net (code "71") (name "unconnected-(U2-ADC0_DP0{slash}ADC1_DP3-Pad9)") (class "Default")
      (node (ref "U2") (pin "9") (pinfunction "ADC0_DP0/ADC1_DP3_9") (pintype "bidirectional"))
    )
    (net (code "72") (name "unconnected-(U2-ADC1_DM0{slash}ADC0_DM3-Pad12)") (class "Default")
      (node (ref "U2") (pin "12") (pinfunction "ADC1_DM0/ADC0_DM3_12") (pintype "bidirectional"))
    )
    (net (code "73") (name "unconnected-(U2-ADC1_DP0{slash}ADC0_DP3-Pad11)") (class "Default")
      (node (ref "U2") (pin "11") (pinfunction "ADC1_DP0/ADC0_DP3_11") (pintype "bidirectional"))
    )
    (net (code "74") (name "unconnected-(U2-DAC0_OUT{slash}CMP1_IN3{slash}ADC0_SE23-Pad18)") (class "Default")
      (node (ref "U2") (pin "18") (pinfunction "DAC0_OUT/CMP1_IN3/ADC0_SE23_18") (pintype "bidirectional"))
    )
    (net (code "75") (name "unconnected-(U2-DAC1_OUT{slash}CMP0_IN4{slash}ADC1_SE23-Pad19)") (class "Default")
      (node (ref "U2") (pin "19") (pinfunction "DAC1_OUT/CMP0_IN4/ADC1_SE23_19") (pintype "bidirectional"))
    )
    (net (code "76") (name "unconnected-(U2-PTA1-Pad23)") (class "Default")
      (node (ref "U2") (pin "23") (pinfunction "PTA1_23") (pintype "bidirectional"))
    )
    (net (code "77") (name "unconnected-(U2-PTA4{slash}LLWU_P3-Pad26)") (class "Default")
      (node (ref "U2") (pin "26") (pinfunction "PTA4/LLWU_P3_26") (pintype "bidirectional"))
    )
    (net (code "78") (name "unconnected-(U2-PTA19-Pad33)") (class "Default")
      (node (ref "U2") (pin "33") (pinfunction "PTA19_33") (pintype "bidirectional"))
    )
    (net (code "79") (name "unconnected-(U2-PTB0{slash}LLWU_P5-Pad35)") (class "Default")
      (node (ref "U2") (pin "35") (pinfunction "PTB0/LLWU_P5_35") (pintype "bidirectional"))
    )
    (net (code "80") (name "unconnected-(U2-PTB1-Pad36)") (class "Default")
      (node (ref "U2") (pin "36") (pinfunction "PTB1_36") (pintype "bidirectional"))
    )
    (net (code "81") (name "unconnected-(U2-PTB2-Pad37)") (class "Default")
      (node (ref "U2") (pin "37") (pinfunction "PTB2_37") (pintype "bidirectional"))
    )
    (net (code "82") (name "unconnected-(U2-PTB3-Pad38)") (class "Default")
      (node (ref "U2") (pin "38") (pinfunction "PTB3_38") (pintype "bidirectional"))
    )
    (net (code "83") (name "unconnected-(U2-PTB16-Pad39)") (class "Default")
      (node (ref "U2") (pin "39") (pinfunction "PTB16_39") (pintype "bidirectional"))
    )
    (net (code "84") (name "unconnected-(U2-PTB17-Pad40)") (class "Default")
      (node (ref "U2") (pin "40") (pinfunction "PTB17_40") (pintype "bidirectional"))
    )
    (net (code "85") (name "unconnected-(U2-PTB18-Pad41)") (class "Default")
      (node (ref "U2") (pin "41") (pinfunction "PTB18_41") (pintype "bidirectional"))
    )
    (net (code "86") (name "unconnected-(U2-PTB19-Pad42)") (class "Default")
      (node (ref "U2") (pin "42") (pinfunction "PTB19_42") (pintype "bidirectional"))
    )
    (net (code "87") (name "unconnected-(U2-PTC0-Pad43)") (class "Default")
      (node (ref "U2") (pin "43") (pinfunction "PTC0_43") (pintype "bidirectional"))
    )
    (net (code "88") (name "unconnected-(U2-PTC3{slash}LLWU_P7-Pad46)") (class "Default")
      (node (ref "U2") (pin "46") (pinfunction "PTC3/LLWU_P7_46") (pintype "bidirectional"))
    )
    (net (code "89") (name "unconnected-(U2-PTC6{slash}LLWU_P10-Pad51)") (class "Default")
      (node (ref "U2") (pin "51") (pinfunction "PTC6/LLWU_P10_51") (pintype "bidirectional"))
    )
    (net (code "90") (name "unconnected-(U2-PTC7-Pad52)") (class "Default")
      (node (ref "U2") (pin "52") (pinfunction "PTC7_52") (pintype "bidirectional"))
    )
    (net (code "91") (name "unconnected-(U2-PTC8-Pad53)") (class "Default")
      (node (ref "U2") (pin "53") (pinfunction "PTC8_53") (pintype "bidirectional"))
    )
    (net (code "92") (name "unconnected-(U2-PTC9-Pad54)") (class "Default")
      (node (ref "U2") (pin "54") (pinfunction "PTC9_54") (pintype "bidirectional"))
    )
    (net (code "93") (name "unconnected-(U2-PTC10-Pad55)") (class "Default")
      (node (ref "U2") (pin "55") (pinfunction "PTC10_55") (pintype "bidirectional"))
    )
    (net (code "94") (name "unconnected-(U2-PTC11{slash}LLWU_P11-Pad56)") (class "Default")
      (node (ref "U2") (pin "56") (pinfunction "PTC11/LLWU_P11_56") (pintype "bidirectional"))
    )
    (net (code "95") (name "unconnected-(U2-PTD0{slash}LLWU_P12-Pad57)") (class "Default")
      (node (ref "U2") (pin "57") (pinfunction "PTD0/LLWU_P12_57") (pintype "bidirectional"))
    )
    (net (code "96") (name "unconnected-(U2-PTD1-Pad58)") (class "Default")
      (node (ref "U2") (pin "58") (pinfunction "PTD1_58") (pintype "bidirectional"))
    )
    (net (code "97") (name "unconnected-(U2-PTD2{slash}LLWU_P13-Pad59)") (class "Default")
      (node (ref "U2") (pin "59") (pinfunction "PTD2/LLWU_P13_59") (pintype "bidirectional"))
    )
    (net (code "98") (name "unconnected-(U2-PTD3-Pad60)") (class "Default")
      (node (ref "U2") (pin "60") (pinfunction "PTD3_60") (pintype "bidirectional"))
    )
    (net (code "99") (name "unconnected-(U2-PTD4{slash}LLWU_P14-Pad61)") (class "Default")
      (node (ref "U2") (pin "61") (pinfunction "PTD4/LLWU_P14_61") (pintype "bidirectional"))
    )
    (net (code "100") (name "unconnected-(U2-PTD5-Pad62)") (class "Default")
      (node (ref "U2") (pin "62") (pinfunction "PTD5_62") (pintype "bidirectional"))
    )
    (net (code "101") (name "unconnected-(U2-PTD6{slash}LLWU_P15-Pad63)") (class "Default")
      (node (ref "U2") (pin "63") (pinfunction "PTD6/LLWU_P15_63") (pintype "bidirectional"))
    )
    (net (code "102") (name "unconnected-(U2-PTD7-Pad64)") (class "Default")
      (node (ref "U2") (pin "64") (pinfunction "PTD7_64") (pintype "bidirectional"))
    )
    (net (code "103") (name "unconnected-(U2-PTE0{slash}CLKOUT32K-Pad1)") (class "Default")
      (node (ref "U2") (pin "1") (pinfunction "PTE0/CLKOUT32K_1") (pintype "bidirectional"))
    )
    (net (code "104") (name "unconnected-(U2-PTE1{slash}LLWU_P0-Pad2)") (class "Default")
      (node (ref "U2") (pin "2") (pinfunction "PTE1/LLWU_P0_2") (pintype "bidirectional"))
    )
    (net (code "105") (name "unconnected-(U2-PTE16-Pad5)") (class "Default")
      (node (ref "U2") (pin "5") (pinfunction "PTE16_5") (pintype "bidirectional"))
    )
    (net (code "106") (name "unconnected-(U2-PTE17-Pad6)") (class "Default")
      (node (ref "U2") (pin "6") (pinfunction "PTE17_6") (pintype "bidirectional"))
    )
    (net (code "107") (name "unconnected-(U2-PTE18-Pad7)") (class "Default")
      (node (ref "U2") (pin "7") (pinfunction "PTE18_7") (pintype "bidirectional"))
    )
    (net (code "108") (name "unconnected-(U2-PTE19-Pad8)") (class "Default")
      (node (ref "U2") (pin "8") (pinfunction "PTE19_8") (pintype "bidirectional"))
    )
    (net (code "109") (name "unconnected-(U2-VREF_OUT{slash}CMP1_IN5{slash}CMP0_IN5{slash}ADC1_SE18-Pad17)") (class "Default")
      (node (ref "U2") (pin "17") (pinfunction "VREF_OUT/CMP1_IN5/CMP0_IN5/ADC1_SE18_17") (pintype "bidirectional"))
    )
  )
)
